# STM32.net
KiCad netlist of a schematic drawn in Altium Designer
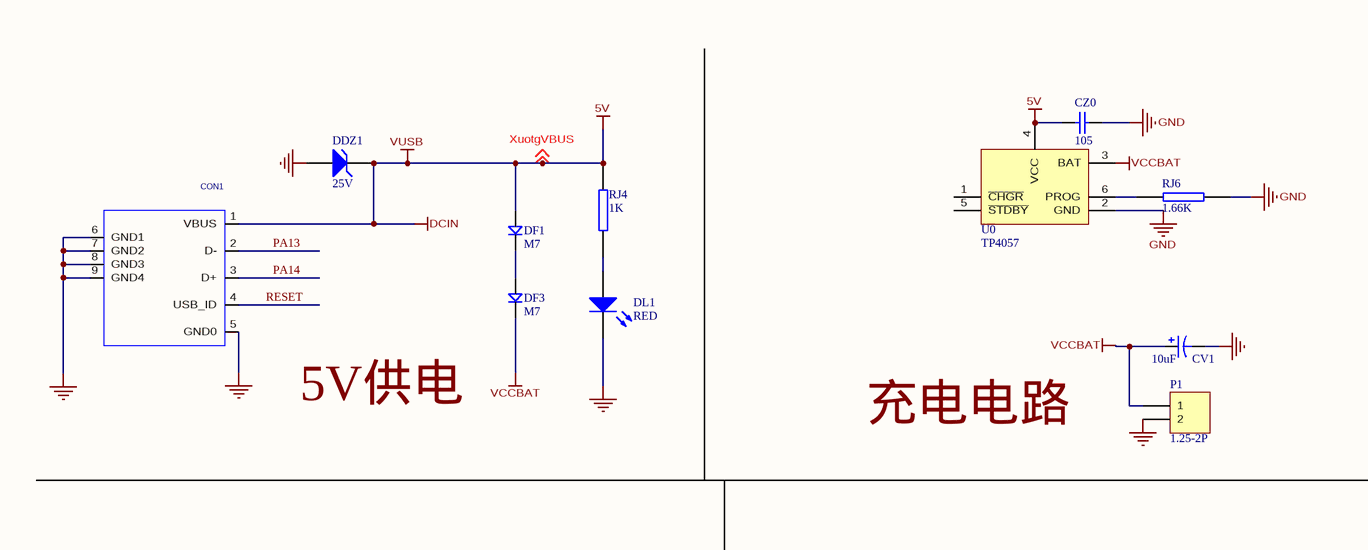
[diagram p0: STM32控制器.schdoc, top left]
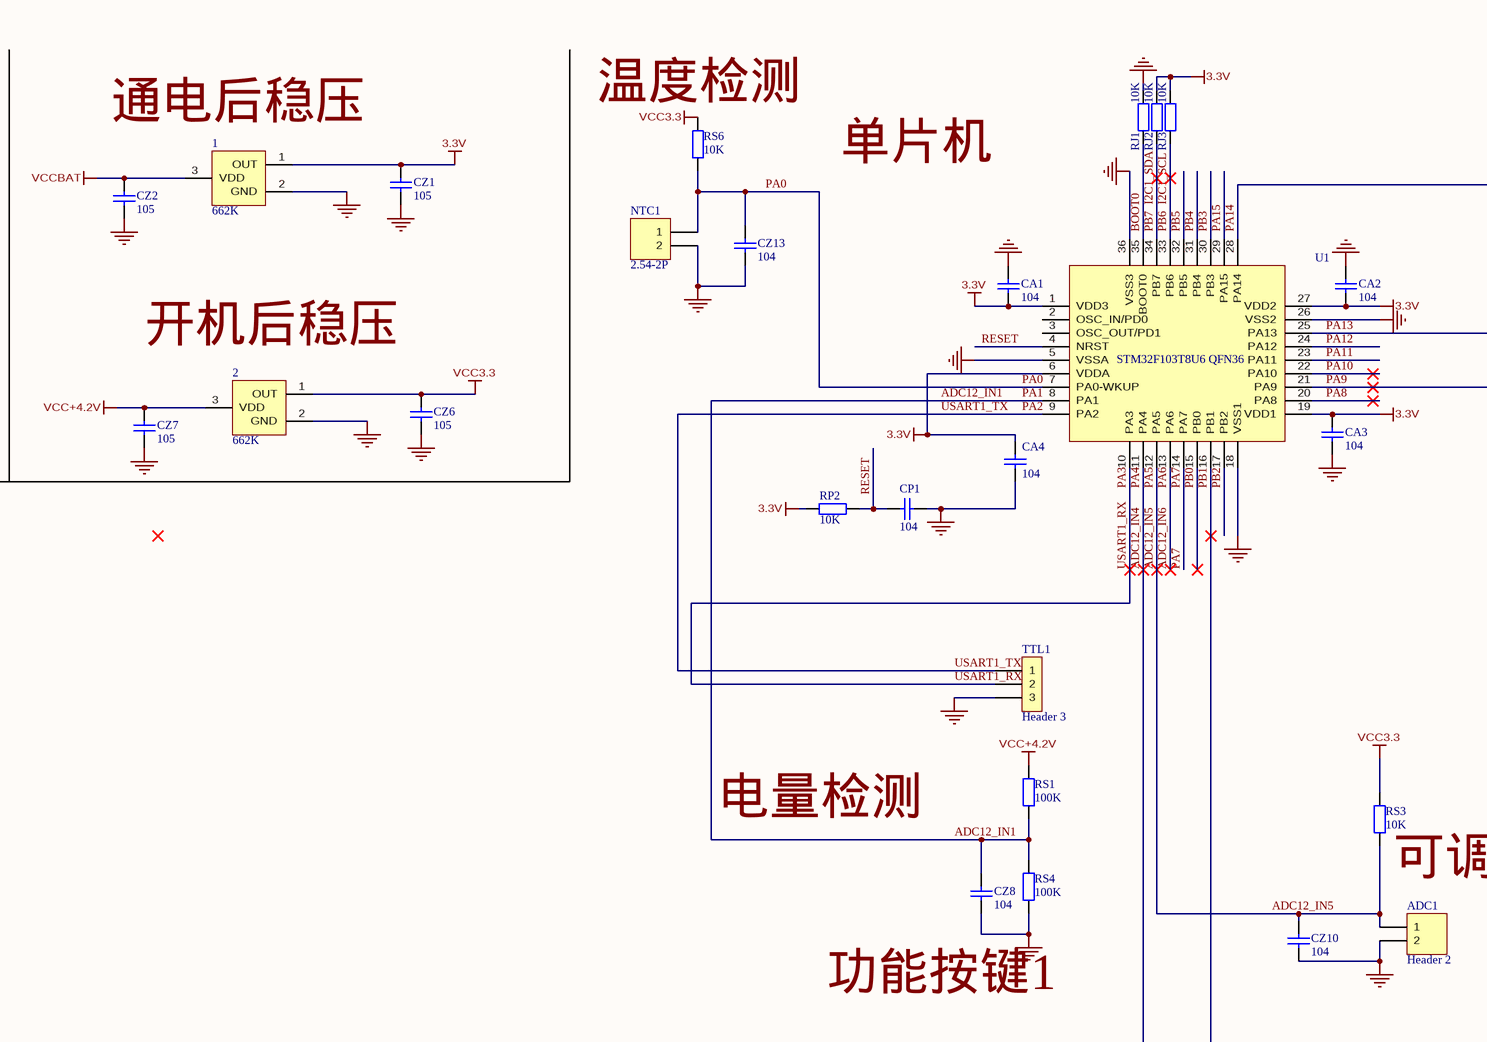
[diagram p1: STM32控制器.schdoc, top middle]
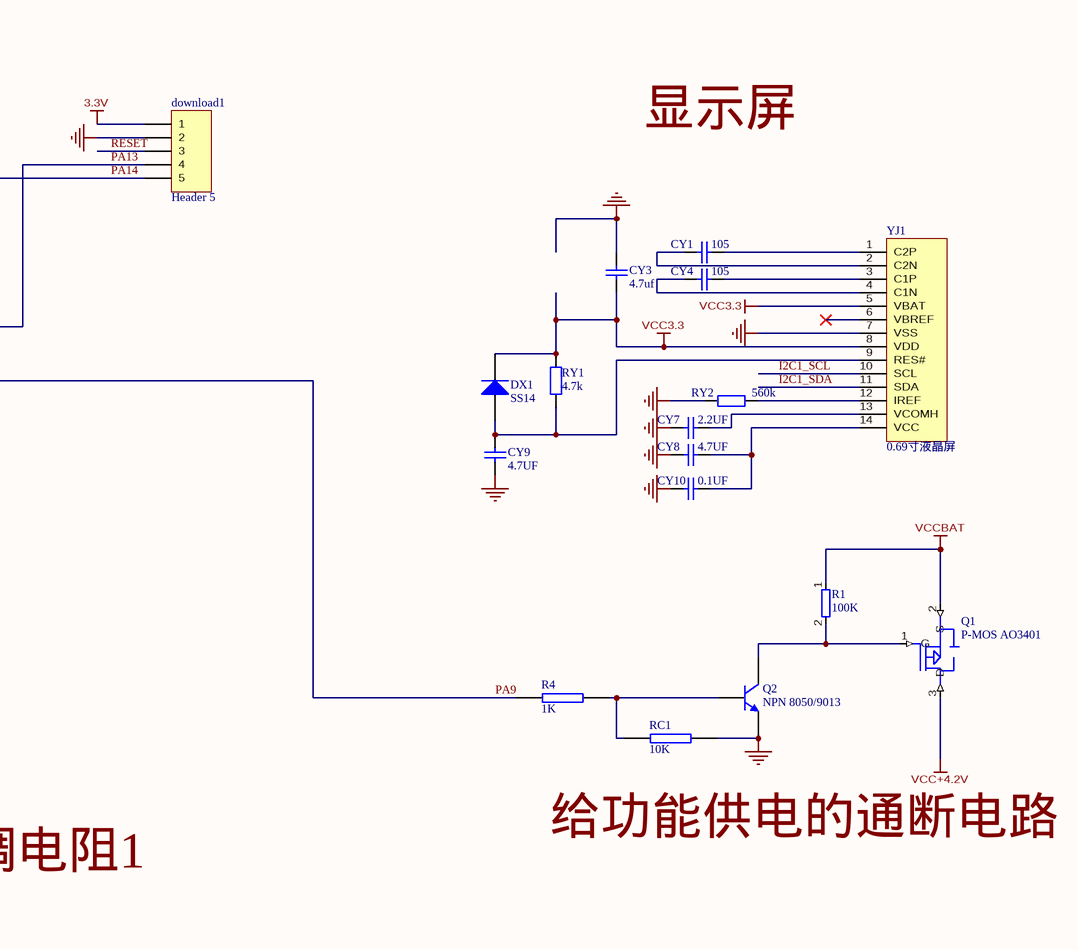
[diagram p2: STM32控制器.schdoc, top right]
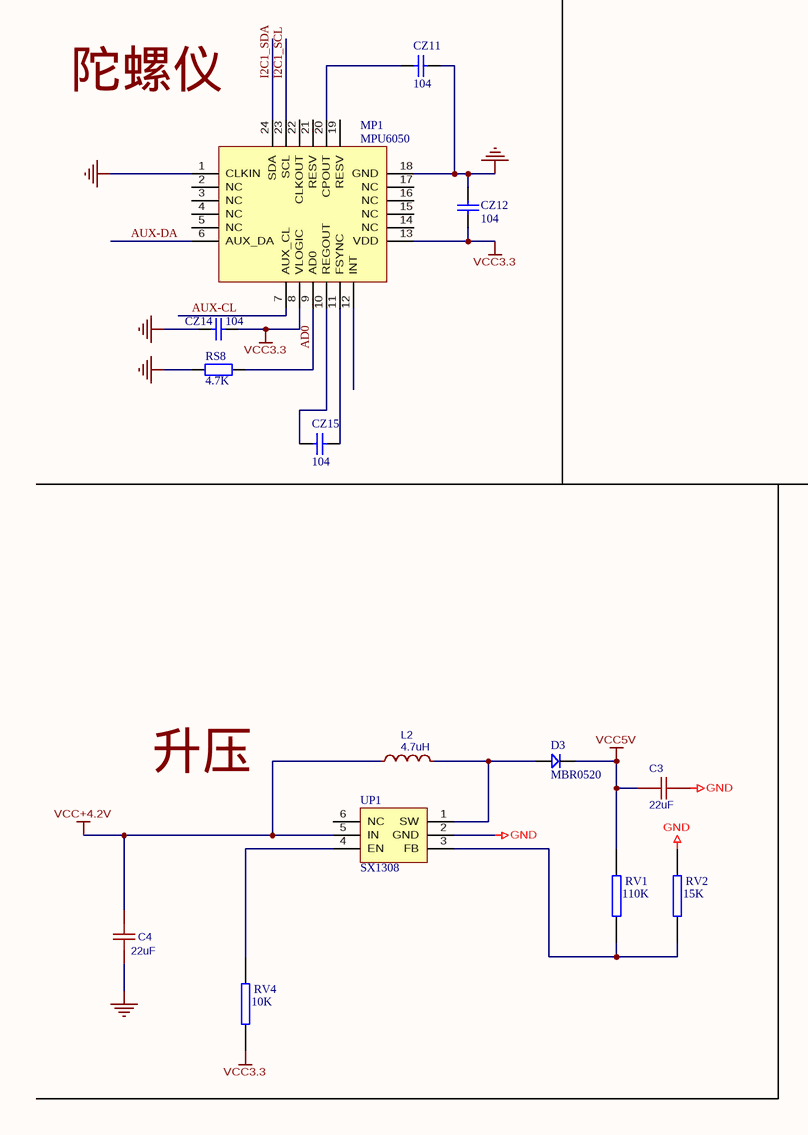
[diagram p3: STM32控制器.schdoc, bottom left]
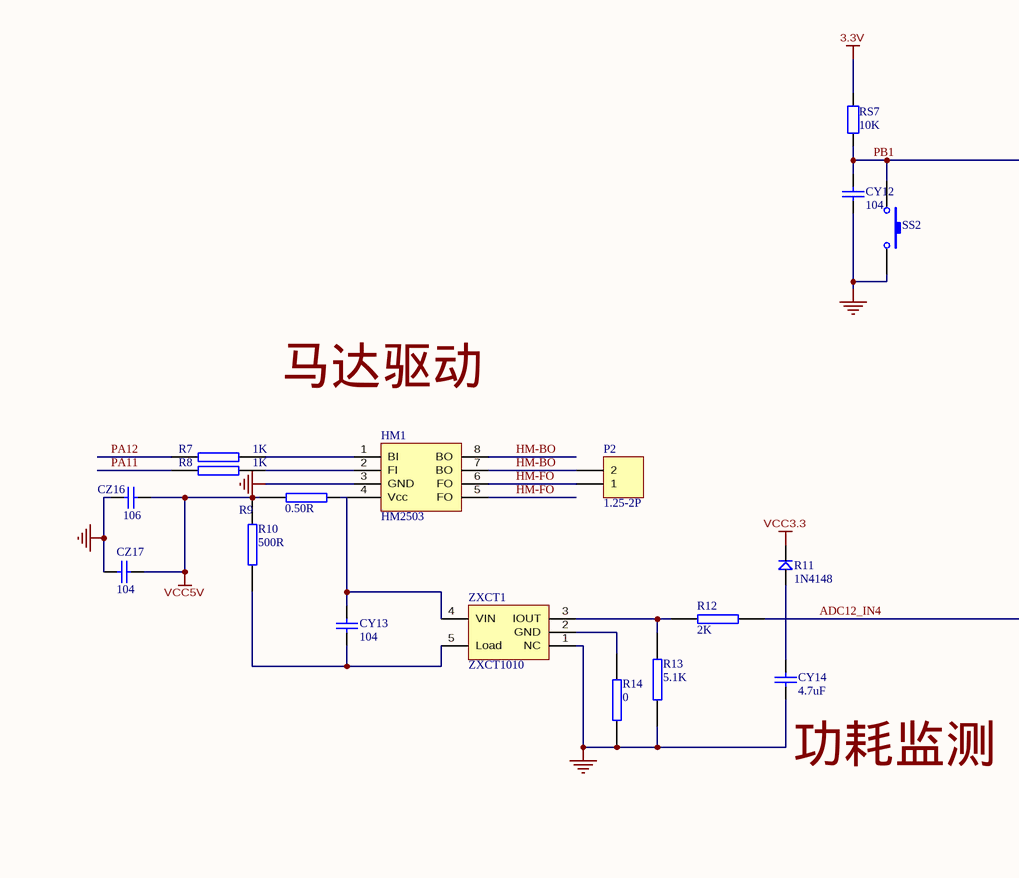
[diagram p4: STM32控制器.schdoc, bottom middle]

(export (version "E")
  (design (tool "Eeschema 10.0.6"))
  (components
    (comp (ref "1") (value "662K") (footprint "SOT23-3-1") (libsource (lib "SCH原理图库") (part "MH5330")))
    (comp (ref "2") (value "662K") (footprint "SOT23-3-1") (libsource (lib "SCH原理图库") (part "MH5330")))
    (comp (ref "ADC1")
      (value "Header 2")
      (footprint "HDR1X2")
      (description "Header, 2-Pin")
      (fields (field (name "PUBLISHER") "Altium Limited"))
      (libsource (lib "SCH原理图库") (part "Header 2"))
    )
    (comp (ref "C3")
      (value "22uF")
      (footprint "0805")
      (fields
        (field (name "VOLTAGE") "25V")
        (field (name "TOLERANCE") "±10%")
        (field (name "BOM_SUPPLIER PART") "C52923")
      )
      (libsource (lib "altium-import") (part "root_2_47uF_"))
    )
    (comp (ref "C4")
      (value "22uF")
      (footprint "0805")
      (fields
        (field (name "VOLTAGE") "25V")
        (field (name "TOLERANCE") "±10%")
        (field (name "BOM_SUPPLIER PART") "C52923")
      )
      (libsource (lib "altium-import") (part "root_1_47uF_"))
    )
    (comp (ref "CA1")
      (value "104")
      (footprint "0402")
      (description "Capacitor")
      (fields (field (name "PUBLISHER") "Altium Limited"))
      (libsource (lib "原理图库") (part "104"))
    )
    (comp (ref "CA2")
      (value "104")
      (footprint "0402")
      (description "Capacitor")
      (fields (field (name "PUBLISHER") "Altium Limited"))
      (libsource (lib "原理图库") (part "104"))
    )
    (comp (ref "CA3")
      (value "104")
      (footprint "0402")
      (description "Capacitor")
      (fields (field (name "PUBLISHER") "Altium Limited"))
      (libsource (lib "原理图库") (part "104"))
    )
    (comp (ref "CA4")
      (value "104")
      (footprint "0402")
      (description "Capacitor")
      (fields (field (name "PUBLISHER") "Altium Limited"))
      (libsource (lib "原理图库") (part "104"))
    )
    (comp (ref "CON1") (value "USB_1") (footprint "USB 贴片 - 2") (libsource (lib "*") (part "USB_1")))
    (comp (ref "CP1")
      (value "104")
      (footprint "0402")
      (description "Capacitor")
      (fields (field (name "PUBLISHER") "Altium Limited"))
      (libsource (lib "原理图库") (part "104"))
    )
    (comp (ref "CV1")
      (value "10uF")
      (footprint "0402")
      (description "Polarized Capacitor (Radial)")
      (libsource (lib "Miscellaneous Devices") (part "Cap Pol1"))
    )
    (comp (ref "CY1")
      (value "105")
      (footprint "0402")
      (description "Capacitor")
      (fields (field (name "PUBLISHER") "Altium Limited"))
      (libsource (lib "原理图库") (part "104"))
    )
    (comp (ref "CY3")
      (value "4.7uf")
      (footprint "0402")
      (description "Capacitor")
      (fields (field (name "PUBLISHER") "Altium Limited"))
      (libsource (lib "Miscellaneous Devices") (part "Cap"))
    )
    (comp (ref "CY4")
      (value "105")
      (footprint "0402")
      (description "Capacitor")
      (fields (field (name "PUBLISHER") "Altium Limited"))
      (libsource (lib "原理图库") (part "104"))
    )
    (comp (ref "CY7")
      (value "2.2UF")
      (footprint "0402")
      (description "Capacitor")
      (fields (field (name "PUBLISHER") "Altium Limited"))
      (libsource (lib "Miscellaneous Devices") (part "Cap"))
    )
    (comp (ref "CY8")
      (value "4.7UF")
      (footprint "0402")
      (description "Capacitor")
      (fields (field (name "PUBLISHER") "Altium Limited"))
      (libsource (lib "Miscellaneous Devices") (part "Cap"))
    )
    (comp (ref "CY9")
      (value "4.7UF")
      (footprint "0402")
      (description "Capacitor")
      (fields (field (name "PUBLISHER") "Altium Limited"))
      (libsource (lib "Miscellaneous Devices") (part "Cap"))
    )
    (comp (ref "CY10")
      (value "0.1UF")
      (footprint "0402")
      (description "Capacitor")
      (fields (field (name "PUBLISHER") "Altium Limited"))
      (libsource (lib "Miscellaneous Devices") (part "Cap"))
    )
    (comp (ref "CY12")
      (value "104")
      (footprint "0402")
      (description "Capacitor")
      (fields (field (name "PUBLISHER") "Altium Limited"))
      (libsource (lib "原理图库") (part "104"))
    )
    (comp (ref "CY13")
      (value "104")
      (footprint "0402")
      (description "Capacitor")
      (fields (field (name "PUBLISHER") "Altium Limited"))
      (libsource (lib "原理图库") (part "104"))
    )
    (comp (ref "CY14")
      (value "4.7uF")
      (footprint "0402")
      (description "Capacitor")
      (fields (field (name "PUBLISHER") "Altium Limited"))
      (libsource (lib "原理图库") (part "104"))
    )
    (comp (ref "CZ0")
      (value "105")
      (footprint "0402")
      (description "Capacitor")
      (fields (field (name "PUBLISHER") "Altium Limited"))
      (libsource (lib "原理图库") (part "104"))
    )
    (comp (ref "CZ1")
      (value "105")
      (footprint "0402")
      (description "Capacitor")
      (libsource (lib "原理图库") (part "104"))
    )
    (comp (ref "CZ2")
      (value "105")
      (footprint "0402")
      (description "Capacitor")
      (libsource (lib "原理图库") (part "104"))
    )
    (comp (ref "CZ6")
      (value "105")
      (footprint "0402")
      (description "Capacitor")
      (libsource (lib "原理图库") (part "104"))
    )
    (comp (ref "CZ7")
      (value "105")
      (footprint "0402")
      (description "Capacitor")
      (libsource (lib "原理图库") (part "104"))
    )
    (comp (ref "CZ8")
      (value "104")
      (footprint "0402")
      (description "Capacitor")
      (libsource (lib "原理图库") (part "104"))
    )
    (comp (ref "CZ10")
      (value "104")
      (footprint "0402")
      (description "Capacitor")
      (fields (field (name "PUBLISHER") "Altium Limited"))
      (libsource (lib "原理图库") (part "104"))
    )
    (comp (ref "CZ11")
      (value "104")
      (footprint "0402")
      (description "Capacitor")
      (libsource (lib "原理图库") (part "104"))
    )
    (comp (ref "CZ12")
      (value "104")
      (footprint "0402")
      (description "Capacitor")
      (libsource (lib "原理图库") (part "104"))
    )
    (comp (ref "CZ13")
      (value "104")
      (footprint "0402")
      (description "Capacitor")
      (libsource (lib "原理图库") (part "104"))
    )
    (comp (ref "CZ14")
      (value "104")
      (footprint "0402")
      (description "Capacitor")
      (libsource (lib "原理图库") (part "104"))
    )
    (comp (ref "CZ15")
      (value "104")
      (footprint "0402")
      (description "Capacitor")
      (libsource (lib "原理图库") (part "104"))
    )
    (comp (ref "CZ16")
      (value "106")
      (footprint "0402")
      (description "Capacitor")
      (libsource (lib "原理图库") (part "104"))
    )
    (comp (ref "CZ17")
      (value "104")
      (footprint "0402")
      (description "Capacitor")
      (libsource (lib "原理图库") (part "104"))
    )
    (comp (ref "D3")
      (value "MBR0520")
      (footprint "SOD-123")
      (description "1N4148")
      (libsource (lib "SCH原理图库") (part "D_1"))
    )
    (comp (ref "DDZ1")
      (value "25V")
      (footprint "DIODE_SOP")
      (description "Zener Diode")
      (libsource (lib "原理图库") (part "D Zener"))
    )
    (comp (ref "DF1") (value "M7") (footprint "DIODE_SOP") (libsource (lib "SCH原理图库") (part "D")))
    (comp (ref "DF3") (value "M7") (footprint "DIODE_SOP") (libsource (lib "SCH原理图库") (part "D")))
    (comp (ref "DL1")
      (value "RED")
      (footprint "0603")
      (description "Typical RED GaAs LED")
      (fields (field (name "PUBLISHER") "Altium Limited"))
      (libsource (lib "原理图库") (part "LED1"))
    )
    (comp (ref "download1")
      (value "Header 5")
      (footprint "HDR1X5")
      (description "Header, 5-Pin")
      (fields (field (name "PUBLISHER") "Altium Limited"))
      (libsource (lib "SCH原理图库") (part "Header 5"))
    )
    (comp (ref "DX1")
      (value "SS14")
      (footprint "0603")
      (description "1 Amp General Purpose Rectifier")
      (fields (field (name "PUBLISHER") "Altium Limited"))
      (libsource (lib "SCH原理图库") (part "Diode 1N4001"))
    )
    (comp (ref "HM1") (value "HM2503") (footprint "SOP-8") (libsource (lib "SCH原理图库") (part "HM2503")))
    (comp (ref "L2")
      (value "4.7uH")
      (footprint "L3*3mm")
      (libsource (lib "altium-import") (part "root_0_2.2uH_"))
    )
    (comp (ref "MP1") (value "MPU6050") (footprint "QFN24") (libsource (lib "SCH原理图库") (part "MPU6050")))
    (comp (ref "NTC1")
      (value "2.54-2P")
      (footprint "HDR1X2")
      (description "Header, 2-Pin")
      (fields (field (name "PUBLISHER") "Altium Limited"))
      (libsource (lib "") (part "Header 2_2"))
    )
    (comp (ref "P1")
      (value "1.25-2P")
      (footprint "1.25卧贴-立式通用-2P")
      (description "Header, 2-Pin")
      (fields (field (name "PUBLISHER") "Altium Limited"))
      (libsource (lib "SCH原理图库") (part "Header 2"))
    )
    (comp (ref "P2")
      (value "1.25-2P")
      (footprint "1.25卧贴-立式通用-2P")
      (description "Header, 2-Pin")
      (fields (field (name "PUBLISHER") "Altium Limited"))
      (libsource (lib "") (part "Header 2_1"))
    )
    (comp (ref "Q1") (value "P-MOS AO3401") (footprint "SOT23") (libsource (lib "*") (part "AO3401")))
    (comp (ref "Q2")
      (value "NPN 8050/9013")
      (footprint "NPN-SOT3")
      (description "NPN Bipolar Transistor")
      (libsource (lib "原理图库") (part "NPN"))
    )
    (comp (ref "R1") (value "100K") (footprint "0402") (libsource (lib "*") (part "RES")))
    (comp (ref "R4") (value "1K") (footprint "0402") (libsource (lib "*") (part "RES2")))
    (comp (ref "R7") (value "1K") (footprint "0402") (libsource (lib "*") (part "RES2")))
    (comp (ref "R8") (value "1K") (footprint "0402") (libsource (lib "*") (part "RES2")))
    (comp (ref "R9") (value "0.50R") (footprint "0805") (libsource (lib "*") (part "RES2")))
    (comp (ref "R10") (value "500R") (footprint "0402") (libsource (lib "*") (part "RES2")))
    (comp (ref "R11") (value "1N4148") (footprint "DIODE_SOP") (libsource (lib "SCH原理图库") (part "D")))
    (comp (ref "R12") (value "2K") (footprint "0402") (libsource (lib "*") (part "RES2")))
    (comp (ref "R13") (value "5.1K") (footprint "0402") (libsource (lib "*") (part "RES2")))
    (comp (ref "R14") (value "0") (footprint "0402") (libsource (lib "*") (part "RES2")))
    (comp (ref "RC1") (value "10K") (footprint "0402") (libsource (lib "*") (part "RES2")))
    (comp (ref "RJ1")
      (value "10K")
      (footprint "0402")
      (description "Resistor")
      (libsource (lib "SCHALL") (part "Res2"))
    )
    (comp (ref "RJ2")
      (value "10K")
      (footprint "0402")
      (description "Resistor")
      (libsource (lib "SCHALL") (part "Res2"))
    )
    (comp (ref "RJ3")
      (value "10K")
      (footprint "0402")
      (description "Resistor")
      (libsource (lib "SCHALL") (part "Res2"))
    )
    (comp (ref "RJ4") (value "1K") (footprint "0402") (libsource (lib "*") (part "RES2")))
    (comp (ref "RJ6") (value "1.66K") (footprint "0402") (libsource (lib "*") (part "RES2")))
    (comp (ref "RP2")
      (value "10K")
      (footprint "0402")
      (description "Resistor")
      (fields (field (name "PUBLISHER") "Altium Limited"))
      (libsource (lib "") (part "Res2_2"))
    )
    (comp (ref "RS1")
      (value "100K")
      (footprint "0402")
      (description "Resistor")
      (libsource (lib "") (part "Res2_1"))
    )
    (comp (ref "RS3")
      (value "10K")
      (footprint "0402")
      (description "Resistor")
      (fields (field (name "PUBLISHER") "Altium Limited"))
      (libsource (lib "") (part "Res2_1"))
    )
    (comp (ref "RS4")
      (value "100K")
      (footprint "0402")
      (description "Resistor")
      (libsource (lib "") (part "Res2_1"))
    )
    (comp (ref "RS6")
      (value "10K")
      (footprint "0402")
      (description "Resistor")
      (libsource (lib "Miscellaneous Devices") (part "Res2"))
    )
    (comp (ref "RS7")
      (value "10K")
      (footprint "0402")
      (description "Resistor")
      (fields (field (name "PUBLISHER") "Altium Limited"))
      (libsource (lib "") (part "Res2_1"))
    )
    (comp (ref "RS8")
      (value "4.7K")
      (footprint "0402")
      (description "Resistor")
      (libsource (lib "") (part "Res2_2"))
    )
    (comp (ref "RV1") (value "110K") (footprint "0402") (libsource (lib "*") (part "RES2")))
    (comp (ref "RV2") (value "15K") (footprint "0402") (libsource (lib "*") (part "RES2")))
    (comp (ref "RV4") (value "10K") (footprint "0402") (libsource (lib "*") (part "RES2")))
    (comp (ref "RY1")
      (value "4.7k")
      (footprint "0402")
      (description "Resistor")
      (fields (field (name "PUBLISHER") "Altium Limited"))
      (libsource (lib "") (part "Res2_3"))
    )
    (comp (ref "RY2")
      (value "560k")
      (footprint "0402")
      (description "Resistor")
      (fields (field (name "PUBLISHER") "Altium Limited"))
      (libsource (lib "") (part "Res2_2"))
    )
    (comp (ref "SS2")
      (value "SW-PB")
      (footprint "SW_smt3*3")
      (description "Switch")
      (fields (field (name "PUBLISHER") "Altium Limited"))
      (libsource (lib "SCH原理图库") (part "SW-PB"))
    )
    (comp (ref "TTL1")
      (value "Header 3")
      (footprint "HDR1X3")
      (description "Header, 3-Pin")
      (fields (field (name "PUBLISHER") "Altium Limited"))
      (libsource (lib "SCH原理图库") (part "Header 3"))
    )
    (comp (ref "U0") (value "TP4057") (footprint "SOT23-6") (libsource (lib "SCH原理图库") (part "TP4057")))
    (comp (ref "U1") (value "STM32F103T8U6 QFN36") (libsource (lib "SCH原理图库") (part "STM32F103T8U6 QFN36")))
    (comp (ref "UP1") (value "SX1308") (footprint "SOT23-6") (libsource (lib "SCH原理图库") (part "SX1308")))
    (comp (ref "YJ1")
      (value "0.69寸液晶屏")
      (footprint "0.86寸 oled 显示屏")
      (libsource (lib "SCH原理图库") (part "0.86寸液晶屏"))
    )
    (comp (ref "ZXCT1")
      (value "ZXCT1010")
      (footprint "SOT23-5")
      (libsource (lib "SCH原理图库") (part "ZXCT1010"))
    )
  )
  (nets
    (net (code "2") (name "/AD0") (class "Default")
      (node (ref "MP1") (pin "9") (pinfunction "AD0_9") (pintype "passive"))
      (node (ref "RS8") (pin "2") (pinfunction "2_2") (pintype "passive"))
    )
    (net (code "3") (name "/ADC12_IN1") (class "Default")
      (node (ref "CZ8") (pin "2") (pinfunction "2_2") (pintype "passive"))
      (node (ref "RS1") (pin "2") (pinfunction "2_2") (pintype "passive"))
      (node (ref "RS4") (pin "1") (pinfunction "1_1") (pintype "passive"))
      (node (ref "U1") (pin "8") (pinfunction "PA1_8") (pintype "passive"))
    )
    (net (code "4") (name "/ADC12_IN4") (class "Default")
      (node (ref "R12") (pin "1") (pinfunction "1_1") (pintype "passive"))
      (node (ref "U1") (pin "11") (pinfunction "PA4_11") (pintype "passive"))
    )
    (net (code "5") (name "/ADC12_IN5") (class "Default")
      (node (ref "ADC1") (pin "1") (pinfunction "1_1") (pintype "passive"))
      (node (ref "CZ10") (pin "2") (pinfunction "2_2") (pintype "passive"))
      (node (ref "RS3") (pin "2") (pinfunction "2_2") (pintype "passive"))
      (node (ref "U1") (pin "12") (pinfunction "PA5_12") (pintype "passive"))
    )
    (net (code "6") (name "/ADC12_IN6") (class "Default")
      (node (ref "U1") (pin "13") (pinfunction "PA6_13") (pintype "passive+no_connect"))
    )
    (net (code "7") (name "/AUX-CL") (class "Default")
      (node (ref "MP1") (pin "7") (pinfunction "AUX_CL_7") (pintype "passive"))
    )
    (net (code "8") (name "/AUX-DA") (class "Default")
      (node (ref "MP1") (pin "6") (pinfunction "AUX_DA_6") (pintype "passive"))
    )
    (net (code "9") (name "/BOOT0") (class "Default")
      (node (ref "RJ1") (pin "1") (pinfunction "1_1") (pintype "passive"))
      (node (ref "U1") (pin "35") (pinfunction "BOOT0_35") (pintype "passive"))
    )
    (net (code "10") (name "/HM-BO") (class "Default")
      (node (ref "HM1") (pin "7") (pinfunction "BO_7") (pintype "passive"))
      (node (ref "HM1") (pin "8") (pinfunction "BO_8") (pintype "passive"))
      (node (ref "P2") (pin "2") (pinfunction "2_2") (pintype "passive"))
    )
    (net (code "11") (name "/HM-FO") (class "Default")
      (node (ref "HM1") (pin "5") (pinfunction "FO_5") (pintype "passive"))
      (node (ref "HM1") (pin "6") (pinfunction "FO_6") (pintype "passive"))
      (node (ref "P2") (pin "1") (pinfunction "1_1") (pintype "passive"))
    )
    (net (code "12") (name "/I2C1_SCL") (class "Default")
      (node (ref "MP1") (pin "23") (pinfunction "SCL_23") (pintype "passive"))
      (node (ref "RJ3") (pin "1") (pinfunction "1_1") (pintype "passive"))
      (node (ref "U1") (pin "33") (pinfunction "PB6_33") (pintype "passive"))
      (node (ref "YJ1") (pin "10") (pinfunction "SCL_10") (pintype "passive"))
    )
    (net (code "13") (name "/I2C1_SDA") (class "Default")
      (node (ref "MP1") (pin "24") (pinfunction "SDA_24") (pintype "passive"))
      (node (ref "RJ2") (pin "1") (pinfunction "1_1") (pintype "passive"))
      (node (ref "U1") (pin "34") (pinfunction "PB7_34") (pintype "passive"))
      (node (ref "YJ1") (pin "11") (pinfunction "SDA_11") (pintype "passive"))
    )
    (net (code "14") (name "/PA0") (class "Default")
      (node (ref "CZ13") (pin "2") (pinfunction "2_2") (pintype "passive"))
      (node (ref "NTC1") (pin "1") (pinfunction "1_1") (pintype "passive"))
      (node (ref "RS6") (pin "2") (pinfunction "2_2") (pintype "passive"))
      (node (ref "U1") (pin "7") (pinfunction "PA0-WKUP_7") (pintype "passive"))
    )
    (net (code "15") (name "/PA2") (class "Default")
      (node (ref "TTL1") (pin "1") (pinfunction "1_1") (pintype "passive"))
      (node (ref "U1") (pin "9") (pinfunction "PA2_9") (pintype "passive"))
    )
    (net (code "16") (name "/PA3") (class "Default")
      (node (ref "TTL1") (pin "2") (pinfunction "2_2") (pintype "passive"))
      (node (ref "U1") (pin "10") (pinfunction "PA3_10") (pintype "passive"))
    )
    (net (code "17") (name "/PA7") (class "Default")
      (node (ref "U1") (pin "14") (pinfunction "PA7_14") (pintype "passive"))
    )
    (net (code "18") (name "/PA8") (class "Default")
      (node (ref "U1") (pin "20") (pinfunction "PA8_20") (pintype "passive"))
    )
    (net (code "19") (name "/PA9") (class "Default")
      (node (ref "R4") (pin "2") (pinfunction "2_2") (pintype "passive"))
      (node (ref "U1") (pin "21") (pinfunction "PA9_21") (pintype "passive"))
    )
    (net (code "20") (name "/PA10") (class "Default")
      (node (ref "U1") (pin "22") (pinfunction "PA10_22") (pintype "passive"))
    )
    (net (code "21") (name "/PA11") (class "Default")
      (node (ref "R8") (pin "2") (pinfunction "2_2") (pintype "passive"))
      (node (ref "U1") (pin "23") (pinfunction "PA11_23") (pintype "passive"))
    )
    (net (code "22") (name "/PA12") (class "Default")
      (node (ref "R7") (pin "2") (pinfunction "2_2") (pintype "passive"))
      (node (ref "U1") (pin "24") (pinfunction "PA12_24") (pintype "passive"))
    )
    (net (code "23") (name "/PA13") (class "Default")
      (node (ref "CON1") (pin "2") (pinfunction "D-_2") (pintype "passive"))
      (node (ref "U1") (pin "25") (pinfunction "PA13_25") (pintype "passive"))
      (node (ref "download1") (pin "4") (pinfunction "4_4") (pintype "passive"))
    )
    (net (code "24") (name "/PA14") (class "Default")
      (node (ref "CON1") (pin "3") (pinfunction "D+_3") (pintype "passive"))
      (node (ref "U1") (pin "28") (pinfunction "PA14_28") (pintype "passive"))
      (node (ref "download1") (pin "5") (pinfunction "5_5") (pintype "passive"))
    )
    (net (code "25") (name "/PA15") (class "Default")
      (node (ref "U1") (pin "29") (pinfunction "PA15_29") (pintype "passive"))
    )
    (net (code "26") (name "/PB0") (class "Default")
      (node (ref "U1") (pin "15") (pinfunction "PB0_15") (pintype "passive+no_connect"))
    )
    (net (code "27") (name "/PB1") (class "Default")
      (node (ref "CY12") (pin "1") (pinfunction "1_1") (pintype "passive"))
      (node (ref "RS7") (pin "2") (pinfunction "2_2") (pintype "passive"))
      (node (ref "SS2") (pin "1") (pinfunction "1_1") (pintype "passive"))
      (node (ref "U1") (pin "16") (pinfunction "PB1_16") (pintype "passive"))
    )
    (net (code "28") (name "/PB2") (class "Default")
      (node (ref "U1") (pin "17") (pinfunction "PB2_17") (pintype "passive"))
    )
    (net (code "29") (name "/PB3") (class "Default")
      (node (ref "U1") (pin "30") (pinfunction "PB3_30") (pintype "passive"))
    )
    (net (code "30") (name "/PB4") (class "Default")
      (node (ref "U1") (pin "31") (pinfunction "PB4_31") (pintype "passive"))
    )
    (net (code "31") (name "/PB5") (class "Default")
      (node (ref "U1") (pin "32") (pinfunction "PB5_32") (pintype "passive"))
    )
    (net (code "32") (name "/RESET") (class "Default")
      (node (ref "CON1") (pin "4") (pinfunction "USB_ID_4") (pintype "passive"))
      (node (ref "CP1") (pin "1") (pinfunction "1_1") (pintype "passive"))
      (node (ref "RP2") (pin "2") (pinfunction "2_2") (pintype "passive"))
      (node (ref "U1") (pin "4") (pinfunction "NRST_4") (pintype "passive"))
      (node (ref "download1") (pin "3") (pinfunction "3_3") (pintype "passive"))
    )
    (net (code "47") (name "3.3V") (class "Default")
      (node (ref "1") (pin "1") (pinfunction "OUT_1") (pintype "passive"))
      (node (ref "CA1") (pin "1") (pinfunction "1_1") (pintype "passive"))
      (node (ref "CA2") (pin "1") (pinfunction "1_1") (pintype "passive"))
      (node (ref "CA3") (pin "1") (pinfunction "1_1") (pintype "passive"))
      (node (ref "CA4") (pin "1") (pinfunction "1_1") (pintype "passive"))
      (node (ref "CZ1") (pin "1") (pinfunction "1_1") (pintype "passive"))
      (node (ref "RJ2") (pin "2") (pinfunction "2_2") (pintype "passive"))
      (node (ref "RJ3") (pin "2") (pinfunction "2_2") (pintype "passive"))
      (node (ref "RP2") (pin "1") (pinfunction "1_1") (pintype "passive"))
      (node (ref "RS7") (pin "1") (pinfunction "1_1") (pintype "passive"))
      (node (ref "U1") (pin "1") (pinfunction "VDD3_1") (pintype "passive"))
      (node (ref "U1") (pin "19") (pinfunction "VDD1_19") (pintype "passive"))
      (node (ref "U1") (pin "27") (pinfunction "VDD2_27") (pintype "passive"))
      (node (ref "U1") (pin "6") (pinfunction "VDDA_6") (pintype "passive"))
      (node (ref "download1") (pin "1") (pinfunction "1_1") (pintype "passive"))
    )
    (net (code "48") (name "5V") (class "Default")
      (node (ref "CON1") (pin "1") (pinfunction "VBUS_1") (pintype "power_in"))
      (node (ref "CZ0") (pin "2") (pinfunction "2_2") (pintype "passive"))
      (node (ref "DDZ1") (pin "2") (pinfunction "K_2") (pintype "passive"))
      (node (ref "DF1") (pin "1") (pintype "passive"))
      (node (ref "RJ4") (pin "1") (pinfunction "1_1") (pintype "passive"))
      (node (ref "U0") (pin "4") (pinfunction "VCC_4") (pintype "passive"))
    )
    (net (code "49") (name "GND") (class "Default")
      (node (ref "1") (pin "2") (pinfunction "GND_2") (pintype "passive"))
      (node (ref "2") (pin "2") (pinfunction "GND_2") (pintype "passive"))
      (node (ref "ADC1") (pin "2") (pinfunction "2_2") (pintype "passive"))
      (node (ref "C3") (pin "1") (pinfunction "1_1") (pintype "passive"))
      (node (ref "C4") (pin "1") (pinfunction "1_1") (pintype "passive"))
      (node (ref "CA1") (pin "2") (pinfunction "2_2") (pintype "passive"))
      (node (ref "CA2") (pin "2") (pinfunction "2_2") (pintype "passive"))
      (node (ref "CA3") (pin "2") (pinfunction "2_2") (pintype "passive"))
      (node (ref "CA4") (pin "2") (pinfunction "2_2") (pintype "passive"))
      (node (ref "CON1") (pin "5") (pinfunction "GND0_5") (pintype "power_in"))
      (node (ref "CON1") (pin "6") (pinfunction "GND1_6") (pintype "power_in"))
      (node (ref "CON1") (pin "7") (pinfunction "GND2_7") (pintype "passive"))
      (node (ref "CON1") (pin "8") (pinfunction "GND3_8") (pintype "passive"))
      (node (ref "CON1") (pin "9") (pinfunction "GND4_9") (pintype "passive"))
      (node (ref "CP1") (pin "2") (pinfunction "2_2") (pintype "passive"))
      (node (ref "CV1") (pin "2") (pinfunction "2_2") (pintype "passive"))
      (node (ref "CY10") (pin "2") (pinfunction "2_2") (pintype "passive"))
      (node (ref "CY12") (pin "2") (pinfunction "2_2") (pintype "passive"))
      (node (ref "CY14") (pin "2") (pinfunction "2_2") (pintype "passive"))
      (node (ref "CY3") (pin "2") (pinfunction "2_2") (pintype "passive"))
      (node (ref "CY7") (pin "2") (pinfunction "2_2") (pintype "passive"))
      (node (ref "CY8") (pin "2") (pinfunction "2_2") (pintype "passive"))
      (node (ref "CY9") (pin "1") (pinfunction "1_1") (pintype "passive"))
      (node (ref "CZ0") (pin "1") (pinfunction "1_1") (pintype "passive"))
      (node (ref "CZ1") (pin "2") (pinfunction "2_2") (pintype "passive"))
      (node (ref "CZ10") (pin "1") (pinfunction "1_1") (pintype "passive"))
      (node (ref "CZ11") (pin "1") (pinfunction "1_1") (pintype "passive"))
      (node (ref "CZ12") (pin "2") (pinfunction "2_2") (pintype "passive"))
      (node (ref "CZ13") (pin "1") (pinfunction "1_1") (pintype "passive"))
      (node (ref "CZ14") (pin "2") (pinfunction "2_2") (pintype "passive"))
      (node (ref "CZ16") (pin "1") (pinfunction "1_1") (pintype "passive"))
      (node (ref "CZ17") (pin "1") (pinfunction "1_1") (pintype "passive"))
      (node (ref "CZ2") (pin "2") (pinfunction "2_2") (pintype "passive"))
      (node (ref "CZ6") (pin "2") (pinfunction "2_2") (pintype "passive"))
      (node (ref "CZ7") (pin "2") (pinfunction "2_2") (pintype "passive"))
      (node (ref "CZ8") (pin "1") (pinfunction "1_1") (pintype "passive"))
      (node (ref "DDZ1") (pin "1") (pinfunction "A_1") (pintype "passive"))
      (node (ref "DL1") (pin "2") (pinfunction "K_2") (pintype "passive"))
      (node (ref "HM1") (pin "3") (pinfunction "GND_3") (pintype "passive"))
      (node (ref "MP1") (pin "1") (pinfunction "CLKIN_1") (pintype "passive"))
      (node (ref "MP1") (pin "18") (pinfunction "GND_18") (pintype "passive"))
      (node (ref "NTC1") (pin "2") (pinfunction "2_2") (pintype "passive"))
      (node (ref "P1") (pin "2") (pinfunction "2_2") (pintype "passive"))
      (node (ref "Q2") (pin "3") (pinfunction "E_3") (pintype "passive"))
      (node (ref "R13") (pin "1") (pinfunction "1_1") (pintype "passive"))
      (node (ref "R14") (pin "1") (pinfunction "1_1") (pintype "passive"))
      (node (ref "RC1") (pin "1") (pinfunction "1_1") (pintype "passive"))
      (node (ref "RJ1") (pin "2") (pinfunction "2_2") (pintype "passive"))
      (node (ref "RJ6") (pin "2") (pinfunction "2_2") (pintype "passive"))
      (node (ref "RS4") (pin "2") (pinfunction "2_2") (pintype "passive"))
      (node (ref "RS8") (pin "1") (pinfunction "1_1") (pintype "passive"))
      (node (ref "RV2") (pin "2") (pinfunction "2_2") (pintype "passive"))
      (node (ref "RY2") (pin "1") (pinfunction "1_1") (pintype "passive"))
      (node (ref "SS2") (pin "2") (pinfunction "2_2") (pintype "passive"))
      (node (ref "TTL1") (pin "3") (pinfunction "3_3") (pintype "passive"))
      (node (ref "U0") (pin "2") (pinfunction "GND_2") (pintype "passive"))
      (node (ref "U1") (pin "18") (pinfunction "VSS1_18") (pintype "passive"))
      (node (ref "U1") (pin "26") (pinfunction "VSS2_26") (pintype "passive"))
      (node (ref "U1") (pin "36") (pinfunction "VSS3_36") (pintype "passive"))
      (node (ref "U1") (pin "5") (pinfunction "VSSA_5") (pintype "passive"))
      (node (ref "UP1") (pin "2") (pinfunction "GND_2") (pintype "passive"))
      (node (ref "YJ1") (pin "7") (pinfunction "VSS_7") (pintype "passive"))
      (node (ref "ZXCT1") (pin "1") (pinfunction "NC_1") (pintype "passive"))
      (node (ref "download1") (pin "2") (pinfunction "2_2") (pintype "passive"))
    )
    (net (code "50") (name "Net-(CY14-Pad1)") (class "Default")
      (node (ref "CY14") (pin "1") (pinfunction "1_1") (pintype "passive"))
      (node (ref "R11") (pin "1") (pintype "passive"))
    )
    (net (code "51") (name "Net-(DF1-Pad2)") (class "Default")
      (node (ref "DF1") (pin "2") (pintype "passive"))
      (node (ref "DF3") (pin "1") (pintype "passive"))
    )
    (net (code "52") (name "Net-(DL1-A)") (class "Default")
      (node (ref "DL1") (pin "1") (pinfunction "A_1") (pintype "passive"))
      (node (ref "RJ4") (pin "2") (pinfunction "2_2") (pintype "passive"))
    )
    (net (code "53") (name "Net-(DX1-A)") (class "Default")
      (node (ref "CY9") (pin "2") (pinfunction "2_2") (pintype "passive"))
      (node (ref "DX1") (pin "1") (pinfunction "A_1") (pintype "passive"))
      (node (ref "RY1") (pin "1") (pinfunction "1_1") (pintype "passive"))
      (node (ref "YJ1") (pin "9") (pinfunction "RES#_9") (pintype "passive"))
    )
    (net (code "54") (name "Net-(HM1-BI)") (class "Default")
      (node (ref "HM1") (pin "1") (pinfunction "BI_1") (pintype "passive"))
      (node (ref "R7") (pin "1") (pinfunction "1_1") (pintype "passive"))
    )
    (net (code "55") (name "Net-(HM1-FI)") (class "Default")
      (node (ref "HM1") (pin "2") (pinfunction "FI_2") (pintype "passive"))
      (node (ref "R8") (pin "1") (pinfunction "1_1") (pintype "passive"))
    )
    (net (code "56") (name "Net-(HM1-Vcc)") (class "Default")
      (node (ref "HM1") (pin "4") (pinfunction "Vcc_4") (pintype "passive"))
      (node (ref "R9") (pin "2") (pinfunction "2_2") (pintype "passive"))
    )
    (net (code "57") (name "Net-(MP1-CPOUT)") (class "Default")
      (node (ref "CZ11") (pin "2") (pinfunction "2_2") (pintype "passive"))
      (node (ref "MP1") (pin "20") (pinfunction "CPOUT_20") (pintype "passive"))
    )
    (net (code "58") (name "Net-(MP1-FSYNC)") (class "Default")
      (node (ref "CZ15") (pin "1") (pinfunction "1_1") (pintype "passive"))
      (node (ref "MP1") (pin "11") (pinfunction "FSYNC_11") (pintype "passive"))
    )
    (net (code "59") (name "Net-(MP1-REGOUT)") (class "Default")
      (node (ref "CZ15") (pin "2") (pinfunction "2_2") (pintype "passive"))
      (node (ref "MP1") (pin "10") (pinfunction "REGOUT_10") (pintype "passive"))
    )
    (net (code "60") (name "Net-(Q1-G)") (class "Default")
      (node (ref "Q1") (pin "1") (pinfunction "G_1") (pintype "input"))
      (node (ref "Q2") (pin "1") (pinfunction "C_1") (pintype "passive"))
      (node (ref "R1") (pin "2") (pinfunction "2_2") (pintype "passive"))
    )
    (net (code "61") (name "Net-(Q2-B)") (class "Default")
      (node (ref "Q2") (pin "2") (pinfunction "B_2") (pintype "passive"))
      (node (ref "R4") (pin "1") (pinfunction "1_1") (pintype "passive"))
      (node (ref "RC1") (pin "2") (pinfunction "2_2") (pintype "passive"))
    )
    (net (code "62") (name "Net-(U0-PROG)") (class "Default")
      (node (ref "RJ6") (pin "1") (pinfunction "1_1") (pintype "passive"))
      (node (ref "U0") (pin "6") (pinfunction "PROG_6") (pintype "passive"))
    )
    (net (code "63") (name "Net-(UP1-EN)") (class "Default")
      (node (ref "RV4") (pin "2") (pinfunction "2_2") (pintype "passive"))
      (node (ref "UP1") (pin "4") (pinfunction "EN_4") (pintype "passive"))
    )
    (net (code "64") (name "Net-(UP1-FB)") (class "Default")
      (node (ref "RV1") (pin "1") (pinfunction "1_1") (pintype "passive"))
      (node (ref "RV2") (pin "1") (pinfunction "1_1") (pintype "passive"))
      (node (ref "UP1") (pin "3") (pinfunction "FB_3") (pintype "passive"))
    )
    (net (code "65") (name "Net-(UP1-SW)") (class "Default")
      (node (ref "D3") (pin "1") (pintype "passive"))
      (node (ref "L2") (pin "2") (pinfunction "2_2") (pintype "passive"))
      (node (ref "UP1") (pin "1") (pinfunction "SW_1") (pintype "passive"))
    )
    (net (code "66") (name "Net-(YJ1-C1N)") (class "Default")
      (node (ref "CY4") (pin "2") (pinfunction "2_2") (pintype "passive"))
      (node (ref "YJ1") (pin "4") (pinfunction "C1N_4") (pintype "passive"))
    )
    (net (code "67") (name "Net-(YJ1-C1P)") (class "Default")
      (node (ref "CY4") (pin "1") (pinfunction "1_1") (pintype "passive"))
      (node (ref "YJ1") (pin "3") (pinfunction "C1P_3") (pintype "passive"))
    )
    (net (code "68") (name "Net-(YJ1-C2N)") (class "Default")
      (node (ref "CY1") (pin "2") (pinfunction "2_2") (pintype "passive"))
      (node (ref "YJ1") (pin "2") (pinfunction "C2N_2") (pintype "passive"))
    )
    (net (code "69") (name "Net-(YJ1-C2P)") (class "Default")
      (node (ref "CY1") (pin "1") (pinfunction "1_1") (pintype "passive"))
      (node (ref "YJ1") (pin "1") (pinfunction "C2P_1") (pintype "passive"))
    )
    (net (code "70") (name "Net-(YJ1-IREF)") (class "Default")
      (node (ref "RY2") (pin "2") (pinfunction "2_2") (pintype "passive"))
      (node (ref "YJ1") (pin "12") (pinfunction "IREF_12") (pintype "passive"))
    )
    (net (code "71") (name "Net-(YJ1-VCC)") (class "Default")
      (node (ref "CY10") (pin "1") (pinfunction "1_1") (pintype "passive"))
      (node (ref "CY8") (pin "1") (pinfunction "1_1") (pintype "passive"))
      (node (ref "YJ1") (pin "14") (pinfunction "VCC_14") (pintype "passive"))
    )
    (net (code "72") (name "Net-(YJ1-VCOMH)") (class "Default")
      (node (ref "CY7") (pin "1") (pinfunction "1_1") (pintype "passive"))
      (node (ref "YJ1") (pin "13") (pinfunction "VCOMH_13") (pintype "passive"))
    )
    (net (code "73") (name "Net-(ZXCT1-GND)") (class "Default")
      (node (ref "R14") (pin "2") (pinfunction "2_2") (pintype "passive"))
      (node (ref "ZXCT1") (pin "2") (pinfunction "GND_2") (pintype "passive"))
    )
    (net (code "74") (name "Net-(ZXCT1-IOUT)") (class "Default")
      (node (ref "R12") (pin "2") (pinfunction "2_2") (pintype "passive"))
      (node (ref "R13") (pin "2") (pinfunction "2_2") (pintype "passive"))
      (node (ref "ZXCT1") (pin "3") (pinfunction "IOUT_3") (pintype "passive"))
    )
    (net (code "75") (name "Net-(ZXCT1-Load)") (class "Default")
      (node (ref "CY13") (pin "2") (pinfunction "2_2") (pintype "passive"))
      (node (ref "R10") (pin "1") (pinfunction "1_1") (pintype "passive"))
      (node (ref "ZXCT1") (pin "5") (pinfunction "Load_5") (pintype "passive"))
    )
    (net (code "76") (name "Net-(ZXCT1-VIN)") (class "Default")
      (node (ref "CY13") (pin "1") (pinfunction "1_1") (pintype "passive"))
      (node (ref "ZXCT1") (pin "4") (pinfunction "VIN_4") (pintype "passive"))
    )
    (net (code "77") (name "VCC+4.2V") (class "Default")
      (node (ref "2") (pin "3") (pinfunction "VDD_3") (pintype "passive"))
      (node (ref "C4") (pin "2") (pinfunction "2_2") (pintype "passive"))
      (node (ref "CZ7") (pin "1") (pinfunction "1_1") (pintype "passive"))
      (node (ref "L2") (pin "1") (pinfunction "1_1") (pintype "passive"))
      (node (ref "Q1") (pin "3") (pinfunction "D_3") (pintype "input"))
      (node (ref "RS1") (pin "1") (pinfunction "1_1") (pintype "passive"))
      (node (ref "UP1") (pin "5") (pinfunction "IN_5") (pintype "passive"))
    )
    (net (code "78") (name "VCC3.3") (class "Default")
      (node (ref "2") (pin "1") (pinfunction "OUT_1") (pintype "passive"))
      (node (ref "CY3") (pin "1") (pinfunction "1_1") (pintype "passive"))
      (node (ref "CZ12") (pin "1") (pinfunction "1_1") (pintype "passive"))
      (node (ref "CZ14") (pin "1") (pinfunction "1_1") (pintype "passive"))
      (node (ref "CZ6") (pin "1") (pinfunction "1_1") (pintype "passive"))
      (node (ref "DX1") (pin "2") (pinfunction "K_2") (pintype "passive"))
      (node (ref "MP1") (pin "13") (pinfunction "VDD_13") (pintype "passive"))
      (node (ref "MP1") (pin "8") (pinfunction "VLOGIC_8") (pintype "passive"))
      (node (ref "R11") (pin "2") (pintype "passive"))
      (node (ref "RS3") (pin "1") (pinfunction "1_1") (pintype "passive"))
      (node (ref "RS6") (pin "1") (pinfunction "1_1") (pintype "passive"))
      (node (ref "RV4") (pin "1") (pinfunction "1_1") (pintype "passive"))
      (node (ref "RY1") (pin "2") (pinfunction "2_2") (pintype "passive"))
      (node (ref "YJ1") (pin "5") (pinfunction "VBAT_5") (pintype "passive"))
      (node (ref "YJ1") (pin "8") (pinfunction "VDD_8") (pintype "passive"))
    )
    (net (code "79") (name "VCC5V") (class "Default")
      (node (ref "C3") (pin "2") (pinfunction "2_2") (pintype "passive"))
      (node (ref "CZ16") (pin "2") (pinfunction "2_2") (pintype "passive"))
      (node (ref "CZ17") (pin "2") (pinfunction "2_2") (pintype "passive"))
      (node (ref "D3") (pin "2") (pintype "passive"))
      (node (ref "R10") (pin "2") (pinfunction "2_2") (pintype "passive"))
      (node (ref "R9") (pin "1") (pinfunction "1_1") (pintype "passive"))
      (node (ref "RV1") (pin "2") (pinfunction "2_2") (pintype "passive"))
    )
    (net (code "80") (name "VCCBAT") (class "Default")
      (node (ref "1") (pin "3") (pinfunction "VDD_3") (pintype "passive"))
      (node (ref "CV1") (pin "1") (pinfunction "1_1") (pintype "passive"))
      (node (ref "CZ2") (pin "1") (pinfunction "1_1") (pintype "passive"))
      (node (ref "DF3") (pin "2") (pintype "passive"))
      (node (ref "P1") (pin "1") (pinfunction "1_1") (pintype "passive"))
      (node (ref "Q1") (pin "2") (pinfunction "S_2") (pintype "input"))
      (node (ref "R1") (pin "1") (pinfunction "1_1") (pintype "passive"))
      (node (ref "U0") (pin "3") (pinfunction "BAT_3") (pintype "passive"))
    )
    (net (code "81") (name "unconnected-(MP1-CLKOUT-Pad22)") (class "Default")
      (node (ref "MP1") (pin "22") (pinfunction "CLKOUT_22") (pintype "passive"))
    )
    (net (code "82") (name "unconnected-(MP1-INT-Pad12)") (class "Default")
      (node (ref "MP1") (pin "12") (pinfunction "INT_12") (pintype "passive"))
    )
    (net (code "83") (name "unconnected-(MP1-NC-Pad2)") (class "Default")
      (node (ref "MP1") (pin "2") (pinfunction "NC_2") (pintype "passive"))
    )
    (net (code "84") (name "unconnected-(MP1-NC-Pad3)") (class "Default")
      (node (ref "MP1") (pin "3") (pinfunction "NC_3") (pintype "passive"))
    )
    (net (code "85") (name "unconnected-(MP1-NC-Pad4)") (class "Default")
      (node (ref "MP1") (pin "4") (pinfunction "NC_4") (pintype "passive"))
    )
    (net (code "86") (name "unconnected-(MP1-NC-Pad5)") (class "Default")
      (node (ref "MP1") (pin "5") (pinfunction "NC_5") (pintype "passive"))
    )
    (net (code "87") (name "unconnected-(MP1-NC-Pad14)") (class "Default")
      (node (ref "MP1") (pin "14") (pinfunction "NC_14") (pintype "passive"))
    )
    (net (code "88") (name "unconnected-(MP1-NC-Pad15)") (class "Default")
      (node (ref "MP1") (pin "15") (pinfunction "NC_15") (pintype "passive"))
    )
    (net (code "89") (name "unconnected-(MP1-NC-Pad16)") (class "Default")
      (node (ref "MP1") (pin "16") (pinfunction "NC_16") (pintype "passive"))
    )
    (net (code "90") (name "unconnected-(MP1-NC-Pad17)") (class "Default")
      (node (ref "MP1") (pin "17") (pinfunction "NC_17") (pintype "passive"))
    )
    (net (code "91") (name "unconnected-(MP1-RESV-Pad19)") (class "Default")
      (node (ref "MP1") (pin "19") (pinfunction "RESV_19") (pintype "passive"))
    )
    (net (code "92") (name "unconnected-(MP1-RESV-Pad21)") (class "Default")
      (node (ref "MP1") (pin "21") (pinfunction "RESV_21") (pintype "passive"))
    )
    (net (code "93") (name "unconnected-(U0-~{CHGR}-Pad1)") (class "Default")
      (node (ref "U0") (pin "1") (pinfunction "~{CHGR}_1") (pintype "passive"))
    )
    (net (code "94") (name "unconnected-(U0-~{STDBY}-Pad5)") (class "Default")
      (node (ref "U0") (pin "5") (pinfunction "~{STDBY}_5") (pintype "passive"))
    )
    (net (code "95") (name "unconnected-(U1-OSC_IN{slash}PD0-Pad2)") (class "Default")
      (node (ref "U1") (pin "2") (pinfunction "OSC_IN/PD0_2") (pintype "passive"))
    )
    (net (code "96") (name "unconnected-(U1-OSC_OUT{slash}PD1-Pad3)") (class "Default")
      (node (ref "U1") (pin "3") (pinfunction "OSC_OUT/PD1_3") (pintype "passive"))
    )
    (net (code "97") (name "unconnected-(UP1-NC-Pad6)") (class "Default")
      (node (ref "UP1") (pin "6") (pinfunction "NC_6") (pintype "passive"))
    )
    (net (code "98") (name "unconnected-(YJ1-VBREF-Pad6)") (class "Default")
      (node (ref "YJ1") (pin "6") (pinfunction "VBREF_6") (pintype "passive+no_connect"))
    )
  )
)
